# alfie.net
KiCad netlist of a schematic drawn in EAGLE
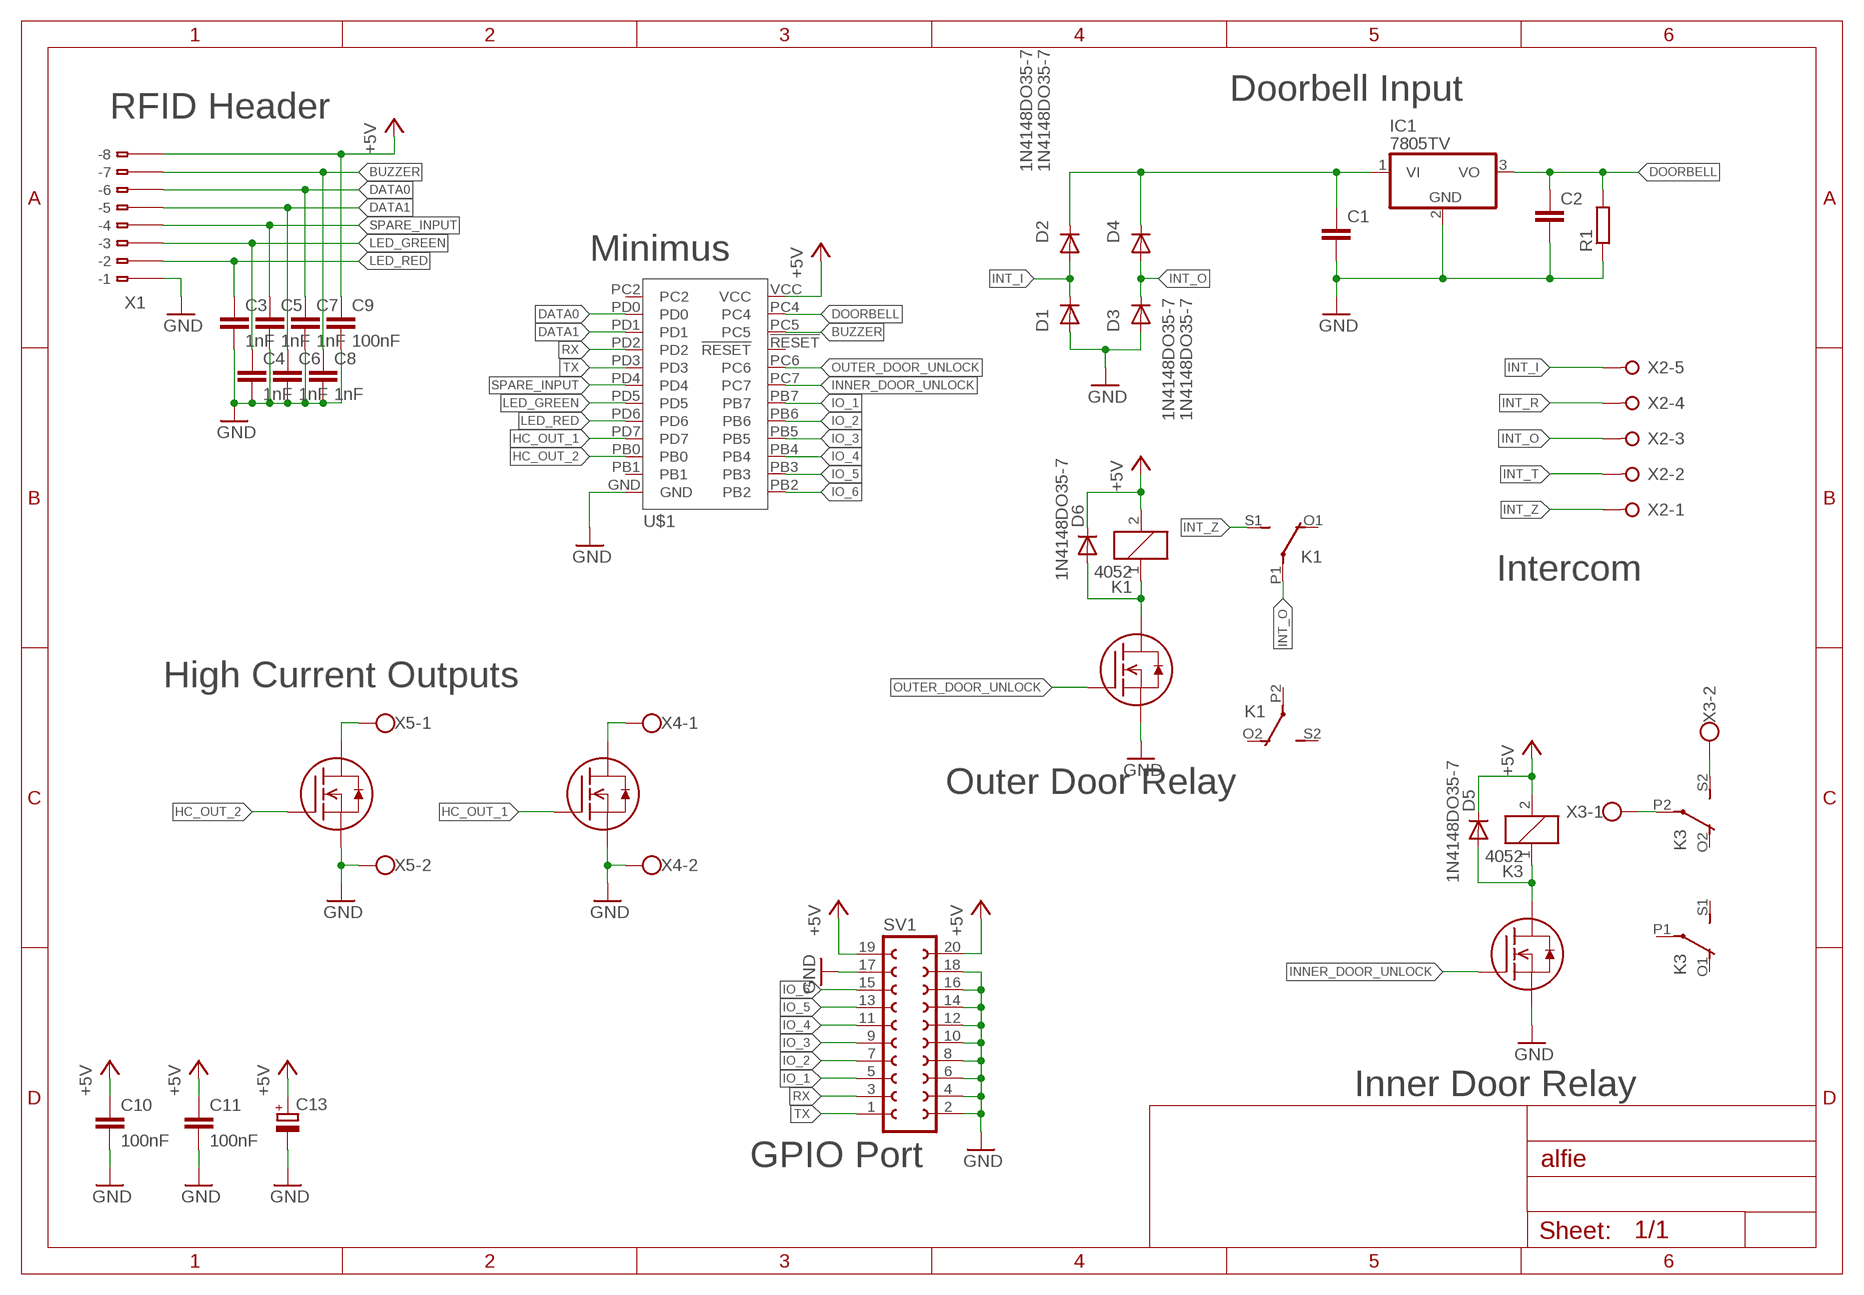
[diagram p0: schematic, sheet 1]

(export (version "E")
  (design (tool "Eeschema 10.0.6"))
  (components
    (comp (ref "C1")
      (value "C-EU025-030X050")
      (footprint "eagle-import:C025-030X050")
      (libsource (lib "eagle-import") (part "C-EU025-030X050"))
    )
    (comp (ref "C2")
      (value "C-EU025-030X050")
      (footprint "eagle-import:C025-030X050")
      (libsource (lib "eagle-import") (part "C-EU025-030X050"))
    )
    (comp (ref "C3")
      (value "1nF")
      (footprint "eagle-import:C0805")
      (libsource (lib "eagle-import") (part "C-EUC0805"))
    )
    (comp (ref "C4")
      (value "1nF")
      (footprint "eagle-import:C0805")
      (libsource (lib "eagle-import") (part "C-EUC0805"))
    )
    (comp (ref "C5")
      (value "1nF")
      (footprint "eagle-import:C0805")
      (libsource (lib "eagle-import") (part "C-EUC0805"))
    )
    (comp (ref "C6")
      (value "1nF")
      (footprint "eagle-import:C0805")
      (libsource (lib "eagle-import") (part "C-EUC0805"))
    )
    (comp (ref "C7")
      (value "1nF")
      (footprint "eagle-import:C0805")
      (libsource (lib "eagle-import") (part "C-EUC0805"))
    )
    (comp (ref "C8")
      (value "1nF")
      (footprint "eagle-import:C0805")
      (libsource (lib "eagle-import") (part "C-EUC0805"))
    )
    (comp (ref "C9")
      (value "100nF")
      (footprint "eagle-import:C0805")
      (libsource (lib "eagle-import") (part "C-EUC0805"))
    )
    (comp (ref "C10")
      (value "100nF")
      (footprint "eagle-import:C0805")
      (libsource (lib "eagle-import") (part "C-EUC0805"))
    )
    (comp (ref "C11")
      (value "100nF")
      (footprint "eagle-import:C0805")
      (libsource (lib "eagle-import") (part "C-EUC0805"))
    )
    (comp (ref "C13")
      (value "CPOL-EUE5-8.5")
      (footprint "eagle-import:E5-8,5")
      (libsource (lib "eagle-import") (part "CPOL-EUE5-8.5"))
    )
    (comp (ref "D1")
      (value "1N4148DO35-7")
      (footprint "eagle-import:DO35-7")
      (libsource (lib "eagle-import") (part "1N4148DO35-7"))
    )
    (comp (ref "D2")
      (value "1N4148DO35-7")
      (footprint "eagle-import:DO35-7")
      (libsource (lib "eagle-import") (part "1N4148DO35-7"))
    )
    (comp (ref "D3")
      (value "1N4148DO35-7")
      (footprint "eagle-import:DO35-7")
      (libsource (lib "eagle-import") (part "1N4148DO35-7"))
    )
    (comp (ref "D4")
      (value "1N4148DO35-7")
      (footprint "eagle-import:DO35-7")
      (libsource (lib "eagle-import") (part "1N4148DO35-7"))
    )
    (comp (ref "D5")
      (value "1N4148DO35-7")
      (footprint "eagle-import:DO35-7")
      (libsource (lib "eagle-import") (part "1N4148DO35-7"))
    )
    (comp (ref "D6")
      (value "1N4148DO35-7")
      (footprint "eagle-import:DO35-7")
      (libsource (lib "eagle-import") (part "1N4148DO35-7"))
    )
    (comp (ref "IC1")
      (value "7805TV")
      (footprint "eagle-import:TO220V")
      (libsource (lib "eagle-import") (part "78TV05"))
    )
    (comp (ref "K1")
      (value "4052")
      (footprint "eagle-import:F4052")
      (fields (field (name "OC_FARNELL") "unknown") (field (name "OC_NEWARK") "unknown"))
      (libsource (lib "eagle-import") (part "4052"))
    )
    (comp (ref "K3")
      (value "4052")
      (footprint "eagle-import:F4052")
      (libsource (lib "eagle-import") (part "4052"))
    )
    (comp (ref "R1")
      (value "R-EU_0207/10")
      (footprint "eagle-import:0207_10")
      (libsource (lib "eagle-import") (part "R-EU_0207/10"))
    )
    (comp (ref "SV1")
      (value "FE10-2")
      (footprint "eagle-import:FE10-2")
      (libsource (lib "eagle-import") (part "FE10-2"))
    )
    (comp (ref "U$1")
      (value "MINIMUS")
      (footprint "eagle-import:MINIMUS")
      (libsource (lib "eagle-import") (part "MINIMUS"))
    )
    (comp (ref "U$2")
      (value "NTF3055L108T1GTAB")
      (footprint "eagle-import:SOT223")
      (libsource (lib "eagle-import") (part "NTF3055L108T1GTAB"))
    )
    (comp (ref "U$3")
      (value "NTF3055L108T1GTAB")
      (footprint "eagle-import:SOT223")
      (libsource (lib "eagle-import") (part "NTF3055L108T1GTAB"))
    )
    (comp (ref "U$4")
      (value "NTF3055L108T1GTAB")
      (footprint "eagle-import:SOT223")
      (libsource (lib "eagle-import") (part "NTF3055L108T1GTAB"))
    )
    (comp (ref "U$5")
      (value "NTF3055L108T1GTAB")
      (footprint "eagle-import:SOT223")
      (libsource (lib "eagle-import") (part "NTF3055L108T1GTAB"))
    )
    (comp (ref "X1")
      (value "233-508")
      (footprint "eagle-import:233-508")
      (fields (field (name "MF") "Wago Corporation") (field (name "MPN") "0233-0508"))
      (libsource (lib "eagle-import") (part "233-508"))
    )
    (comp (ref "X2")
      (value "W237-05P")
      (footprint "eagle-import:W237-5P")
      (libsource (lib "eagle-import") (part "W237-05P"))
    )
    (comp (ref "X3")
      (value "W237-102")
      (footprint "eagle-import:W237-102")
      (fields (field (name "MPN") "237-102"))
      (libsource (lib "eagle-import") (part "W237-102"))
    )
    (comp (ref "X4")
      (value "W237-102")
      (footprint "eagle-import:W237-102")
      (fields (field (name "MPN") "237-102"))
      (libsource (lib "eagle-import") (part "W237-102"))
    )
    (comp (ref "X5")
      (value "W237-102")
      (footprint "eagle-import:W237-102")
      (fields (field (name "MPN") "237-102"))
      (libsource (lib "eagle-import") (part "W237-102"))
    )
  )
  (nets
    (net (code "1") (name "+5V") (class "Default")
      (node (ref "C10") (pin "1") (pinfunction "1_1") (pintype "passive"))
      (node (ref "C11") (pin "1") (pinfunction "1_1") (pintype "passive"))
      (node (ref "C13") (pin "+") (pinfunction "+_+") (pintype "passive"))
      (node (ref "C9") (pin "1") (pinfunction "1_1") (pintype "passive"))
      (node (ref "D5") (pin "C") (pinfunction "C_C") (pintype "passive"))
      (node (ref "D6") (pin "C") (pinfunction "C_C") (pintype "passive"))
      (node (ref "K1") (pin "2") (pinfunction "2_2") (pintype "passive"))
      (node (ref "K3") (pin "2") (pinfunction "2_2") (pintype "passive"))
      (node (ref "SV1") (pin "19") (pinfunction "19_19") (pintype "passive"))
      (node (ref "SV1") (pin "20") (pinfunction "20_20") (pintype "passive"))
      (node (ref "U$1") (pin "VCC") (pinfunction "VCC_VCC") (pintype "power_in"))
      (node (ref "X1") (pin "B8") (pinfunction "B-8_B8") (pintype "passive"))
    )
    (net (code "2") (name "BUZZER") (class "Default")
      (node (ref "C8") (pin "1") (pinfunction "1_1") (pintype "passive"))
      (node (ref "U$1") (pin "PC5") (pinfunction "PC5_PC5") (pintype "bidirectional"))
      (node (ref "X1") (pin "B7") (pinfunction "B-7_B7") (pintype "passive"))
    )
    (net (code "3") (name "DATA0") (class "Default")
      (node (ref "C7") (pin "1") (pinfunction "1_1") (pintype "passive"))
      (node (ref "U$1") (pin "PD0") (pinfunction "PD0_PD0") (pintype "bidirectional"))
      (node (ref "X1") (pin "B6") (pinfunction "B-6_B6") (pintype "passive"))
    )
    (net (code "4") (name "DATA1") (class "Default")
      (node (ref "C6") (pin "1") (pinfunction "1_1") (pintype "passive"))
      (node (ref "U$1") (pin "PD1") (pinfunction "PD1_PD1") (pintype "bidirectional"))
      (node (ref "X1") (pin "B5") (pinfunction "B-5_B5") (pintype "passive"))
    )
    (net (code "5") (name "DOORBELL") (class "Default")
      (node (ref "C2") (pin "1") (pinfunction "1_1") (pintype "passive"))
      (node (ref "IC1") (pin "3") (pinfunction "VO_3") (pintype "passive"))
      (node (ref "R1") (pin "2") (pinfunction "2_2") (pintype "passive"))
      (node (ref "U$1") (pin "PC4") (pinfunction "PC4_PC4") (pintype "bidirectional"))
    )
    (net (code "6") (name "GND") (class "Default")
      (node (ref "C1") (pin "2") (pinfunction "2_2") (pintype "passive"))
      (node (ref "C10") (pin "2") (pinfunction "2_2") (pintype "passive"))
      (node (ref "C11") (pin "2") (pinfunction "2_2") (pintype "passive"))
      (node (ref "C13") (pin "-") (pinfunction "-_-") (pintype "passive"))
      (node (ref "C2") (pin "2") (pinfunction "2_2") (pintype "passive"))
      (node (ref "C3") (pin "2") (pinfunction "2_2") (pintype "passive"))
      (node (ref "C4") (pin "2") (pinfunction "2_2") (pintype "passive"))
      (node (ref "C5") (pin "2") (pinfunction "2_2") (pintype "passive"))
      (node (ref "C6") (pin "2") (pinfunction "2_2") (pintype "passive"))
      (node (ref "C7") (pin "2") (pinfunction "2_2") (pintype "passive"))
      (node (ref "C8") (pin "2") (pinfunction "2_2") (pintype "passive"))
      (node (ref "C9") (pin "2") (pinfunction "2_2") (pintype "passive"))
      (node (ref "D1") (pin "A") (pinfunction "A_A") (pintype "passive"))
      (node (ref "D3") (pin "A") (pinfunction "A_A") (pintype "passive"))
      (node (ref "IC1") (pin "2") (pinfunction "GND_2") (pintype "passive"))
      (node (ref "R1") (pin "1") (pinfunction "1_1") (pintype "passive"))
      (node (ref "SV1") (pin "10") (pinfunction "10_10") (pintype "passive"))
      (node (ref "SV1") (pin "12") (pinfunction "12_12") (pintype "passive"))
      (node (ref "SV1") (pin "14") (pinfunction "14_14") (pintype "passive"))
      (node (ref "SV1") (pin "16") (pinfunction "16_16") (pintype "passive"))
      (node (ref "SV1") (pin "17") (pinfunction "17_17") (pintype "passive"))
      (node (ref "SV1") (pin "18") (pinfunction "18_18") (pintype "passive"))
      (node (ref "SV1") (pin "2") (pinfunction "2_2") (pintype "passive"))
      (node (ref "SV1") (pin "4") (pinfunction "4_4") (pintype "passive"))
      (node (ref "SV1") (pin "6") (pinfunction "6_6") (pintype "passive"))
      (node (ref "SV1") (pin "8") (pinfunction "8_8") (pintype "passive"))
      (node (ref "U$1") (pin "GND") (pinfunction "GND_GND") (pintype "power_in"))
      (node (ref "U$2") (pin "3") (pinfunction "S_3") (pintype "passive"))
      (node (ref "U$3") (pin "3") (pinfunction "S_3") (pintype "passive"))
      (node (ref "U$4") (pin "3") (pinfunction "S_3") (pintype "passive"))
      (node (ref "U$5") (pin "3") (pinfunction "S_3") (pintype "passive"))
      (node (ref "X1") (pin "B1") (pinfunction "B-1_B1") (pintype "passive"))
      (node (ref "X4") (pin "2") (pinfunction "KL_2") (pintype "passive"))
      (node (ref "X5") (pin "2") (pinfunction "KL_2") (pintype "passive"))
    )
    (net (code "7") (name "HC_OUT_1") (class "Default")
      (node (ref "U$1") (pin "PD7") (pinfunction "PD7_PD7") (pintype "bidirectional"))
      (node (ref "U$3") (pin "1") (pinfunction "G_1") (pintype "passive"))
    )
    (net (code "8") (name "HC_OUT_2") (class "Default")
      (node (ref "U$1") (pin "PB0") (pinfunction "PB0_PB0") (pintype "bidirectional"))
      (node (ref "U$4") (pin "1") (pinfunction "G_1") (pintype "passive"))
    )
    (net (code "9") (name "INNER_DOOR_UNLOCK") (class "Default")
      (node (ref "U$1") (pin "PC7") (pinfunction "PC7_PC7") (pintype "bidirectional"))
      (node (ref "U$5") (pin "1") (pinfunction "G_1") (pintype "passive"))
    )
    (net (code "10") (name "INT_I") (class "Default")
      (node (ref "D1") (pin "C") (pinfunction "C_C") (pintype "passive"))
      (node (ref "D2") (pin "A") (pinfunction "A_A") (pintype "passive"))
      (node (ref "X2") (pin "5") (pinfunction "KL_5") (pintype "passive"))
    )
    (net (code "11") (name "INT_O") (class "Default")
      (node (ref "D3") (pin "C") (pinfunction "C_C") (pintype "passive"))
      (node (ref "D4") (pin "A") (pinfunction "A_A") (pintype "passive"))
      (node (ref "K1") (pin "P1") (pinfunction "P_P1") (pintype "passive"))
      (node (ref "X2") (pin "3") (pinfunction "KL_3") (pintype "passive"))
    )
    (net (code "12") (name "INT_R") (class "Default")
      (node (ref "X2") (pin "4") (pinfunction "KL_4") (pintype "passive"))
    )
    (net (code "13") (name "INT_T") (class "Default")
      (node (ref "X2") (pin "2") (pinfunction "KL_2") (pintype "passive"))
    )
    (net (code "14") (name "INT_Z") (class "Default")
      (node (ref "K1") (pin "S1") (pinfunction "S_S1") (pintype "passive"))
      (node (ref "X2") (pin "1") (pinfunction "KL_1") (pintype "passive"))
    )
    (net (code "15") (name "IO_1") (class "Default")
      (node (ref "SV1") (pin "5") (pinfunction "5_5") (pintype "passive"))
      (node (ref "U$1") (pin "PB7") (pinfunction "PB7_PB7") (pintype "bidirectional"))
    )
    (net (code "16") (name "IO_2") (class "Default")
      (node (ref "SV1") (pin "7") (pinfunction "7_7") (pintype "passive"))
      (node (ref "U$1") (pin "PB6") (pinfunction "PB6_PB6") (pintype "bidirectional"))
    )
    (net (code "17") (name "IO_3") (class "Default")
      (node (ref "SV1") (pin "9") (pinfunction "9_9") (pintype "passive"))
      (node (ref "U$1") (pin "PB5") (pinfunction "PB5_PB5") (pintype "bidirectional"))
    )
    (net (code "18") (name "IO_4") (class "Default")
      (node (ref "SV1") (pin "11") (pinfunction "11_11") (pintype "passive"))
      (node (ref "U$1") (pin "PB4") (pinfunction "PB4_PB4") (pintype "bidirectional"))
    )
    (net (code "19") (name "IO_5") (class "Default")
      (node (ref "SV1") (pin "13") (pinfunction "13_13") (pintype "passive"))
      (node (ref "U$1") (pin "PB3") (pinfunction "PB3_PB3") (pintype "bidirectional"))
    )
    (net (code "20") (name "IO_6") (class "Default")
      (node (ref "SV1") (pin "15") (pinfunction "15_15") (pintype "passive"))
      (node (ref "U$1") (pin "PB2") (pinfunction "PB2_PB2") (pintype "bidirectional"))
    )
    (net (code "21") (name "LED_GREEN") (class "Default")
      (node (ref "C4") (pin "1") (pinfunction "1_1") (pintype "passive"))
      (node (ref "U$1") (pin "PD5") (pinfunction "PD5_PD5") (pintype "bidirectional"))
      (node (ref "X1") (pin "B3") (pinfunction "B-3_B3") (pintype "passive"))
    )
    (net (code "22") (name "LED_RED") (class "Default")
      (node (ref "C3") (pin "1") (pinfunction "1_1") (pintype "passive"))
      (node (ref "U$1") (pin "PD6") (pinfunction "PD6_PD6") (pintype "bidirectional"))
      (node (ref "X1") (pin "B2") (pinfunction "B-2_B2") (pintype "passive"))
    )
    (net (code "23") (name "Net-(IC1-VI)") (class "Default")
      (node (ref "C1") (pin "1") (pinfunction "1_1") (pintype "passive"))
      (node (ref "D2") (pin "C") (pinfunction "C_C") (pintype "passive"))
      (node (ref "D4") (pin "C") (pinfunction "C_C") (pintype "passive"))
      (node (ref "IC1") (pin "1") (pinfunction "VI_1") (pintype "input"))
    )
    (net (code "24") (name "Net-(K3C-P)") (class "Default")
      (node (ref "K3") (pin "P2") (pinfunction "P_P2") (pintype "passive"))
      (node (ref "X3") (pin "1") (pinfunction "KL_1") (pintype "passive"))
    )
    (net (code "25") (name "Net-(K3C-S)") (class "Default")
      (node (ref "K3") (pin "S2") (pinfunction "S_S2") (pintype "passive"))
      (node (ref "X3") (pin "2") (pinfunction "KL_2") (pintype "passive"))
    )
    (net (code "26") (name "Net-(U$2-D)") (class "Default")
      (node (ref "D6") (pin "A") (pinfunction "A_A") (pintype "passive"))
      (node (ref "K1") (pin "1") (pinfunction "1_1") (pintype "passive"))
      (node (ref "U$2") (pin "4") (pinfunction "D_4") (pintype "passive"))
    )
    (net (code "27") (name "Net-(U$3-D)") (class "Default")
      (node (ref "U$3") (pin "4") (pinfunction "D_4") (pintype "passive"))
      (node (ref "X4") (pin "1") (pinfunction "KL_1") (pintype "passive"))
    )
    (net (code "28") (name "Net-(U$4-D)") (class "Default")
      (node (ref "U$4") (pin "4") (pinfunction "D_4") (pintype "passive"))
      (node (ref "X5") (pin "1") (pinfunction "KL_1") (pintype "passive"))
    )
    (net (code "29") (name "Net-(U$5-D)") (class "Default")
      (node (ref "D5") (pin "A") (pinfunction "A_A") (pintype "passive"))
      (node (ref "K3") (pin "1") (pinfunction "1_1") (pintype "passive"))
      (node (ref "U$5") (pin "4") (pinfunction "D_4") (pintype "passive"))
    )
    (net (code "30") (name "OUTER_DOOR_UNLOCK") (class "Default")
      (node (ref "U$1") (pin "PC6") (pinfunction "PC6_PC6") (pintype "bidirectional"))
      (node (ref "U$2") (pin "1") (pinfunction "G_1") (pintype "passive"))
    )
    (net (code "31") (name "RX") (class "Default")
      (node (ref "SV1") (pin "3") (pinfunction "3_3") (pintype "passive"))
      (node (ref "U$1") (pin "PD2") (pinfunction "PD2_PD2") (pintype "bidirectional"))
    )
    (net (code "32") (name "SPARE_INPUT") (class "Default")
      (node (ref "C5") (pin "1") (pinfunction "1_1") (pintype "passive"))
      (node (ref "U$1") (pin "PD4") (pinfunction "PD4_PD4") (pintype "bidirectional"))
      (node (ref "X1") (pin "B4") (pinfunction "B-4_B4") (pintype "passive"))
    )
    (net (code "33") (name "TX") (class "Default")
      (node (ref "SV1") (pin "1") (pinfunction "1_1") (pintype "passive"))
      (node (ref "U$1") (pin "PD3") (pinfunction "PD3_PD3") (pintype "bidirectional"))
    )
    (net (code "34") (name "unconnected-(K1B-O-PadO1)") (class "Default")
      (node (ref "K1") (pin "O1") (pinfunction "O_O1") (pintype "passive"))
    )
    (net (code "35") (name "unconnected-(K1C-O-PadO2)") (class "Default")
      (node (ref "K1") (pin "O2") (pinfunction "O_O2") (pintype "passive"))
    )
    (net (code "36") (name "unconnected-(K1C-P-PadP2)") (class "Default")
      (node (ref "K1") (pin "P2") (pinfunction "P_P2") (pintype "passive"))
    )
    (net (code "37") (name "unconnected-(K1C-S-PadS2)") (class "Default")
      (node (ref "K1") (pin "S2") (pinfunction "S_S2") (pintype "passive"))
    )
    (net (code "38") (name "unconnected-(K3B-O-PadO1)") (class "Default")
      (node (ref "K3") (pin "O1") (pinfunction "O_O1") (pintype "passive"))
    )
    (net (code "39") (name "unconnected-(K3B-P-PadP1)") (class "Default")
      (node (ref "K3") (pin "P1") (pinfunction "P_P1") (pintype "passive"))
    )
    (net (code "40") (name "unconnected-(K3B-S-PadS1)") (class "Default")
      (node (ref "K3") (pin "S1") (pinfunction "S_S1") (pintype "passive"))
    )
    (net (code "41") (name "unconnected-(K3C-O-PadO2)") (class "Default")
      (node (ref "K3") (pin "O2") (pinfunction "O_O2") (pintype "passive"))
    )
    (net (code "42") (name "unconnected-(U$1-PadPB1)") (class "Default")
      (node (ref "U$1") (pin "PB1") (pinfunction "PB1_PB1") (pintype "bidirectional"))
    )
    (net (code "43") (name "unconnected-(U$1-PadPC2)") (class "Default")
      (node (ref "U$1") (pin "PC2") (pinfunction "PC2_PC2") (pintype "bidirectional"))
    )
    (net (code "44") (name "unconnected-(U$1-~{RESET}-Pad!RESET)") (class "Default")
      (node (ref "U$1") (pin "!RESET") (pinfunction "~{RESET}_!RESET") (pintype "input"))
    )
    (net (code "45") (name "unconnected-(X1--1-PadA1)") (class "Default")
      (node (ref "X1") (pin "A1") (pinfunction "-1_A1") (pintype "passive"))
    )
    (net (code "46") (name "unconnected-(X1--2-PadA2)") (class "Default")
      (node (ref "X1") (pin "A2") (pinfunction "-2_A2") (pintype "passive"))
    )
    (net (code "47") (name "unconnected-(X1--3-PadA3)") (class "Default")
      (node (ref "X1") (pin "A3") (pinfunction "-3_A3") (pintype "passive"))
    )
    (net (code "48") (name "unconnected-(X1--4-PadA4)") (class "Default")
      (node (ref "X1") (pin "A4") (pinfunction "-4_A4") (pintype "passive"))
    )
    (net (code "49") (name "unconnected-(X1--5-PadA5)") (class "Default")
      (node (ref "X1") (pin "A5") (pinfunction "-5_A5") (pintype "passive"))
    )
    (net (code "50") (name "unconnected-(X1--6-PadA6)") (class "Default")
      (node (ref "X1") (pin "A6") (pinfunction "-6_A6") (pintype "passive"))
    )
    (net (code "51") (name "unconnected-(X1--7-PadA7)") (class "Default")
      (node (ref "X1") (pin "A7") (pinfunction "-7_A7") (pintype "passive"))
    )
    (net (code "52") (name "unconnected-(X1--8-PadA8)") (class "Default")
      (node (ref "X1") (pin "A8") (pinfunction "-8_A8") (pintype "passive"))
    )
  )
)
